# FPGA.net
KiCad netlist of a schematic drawn in Altium Designer
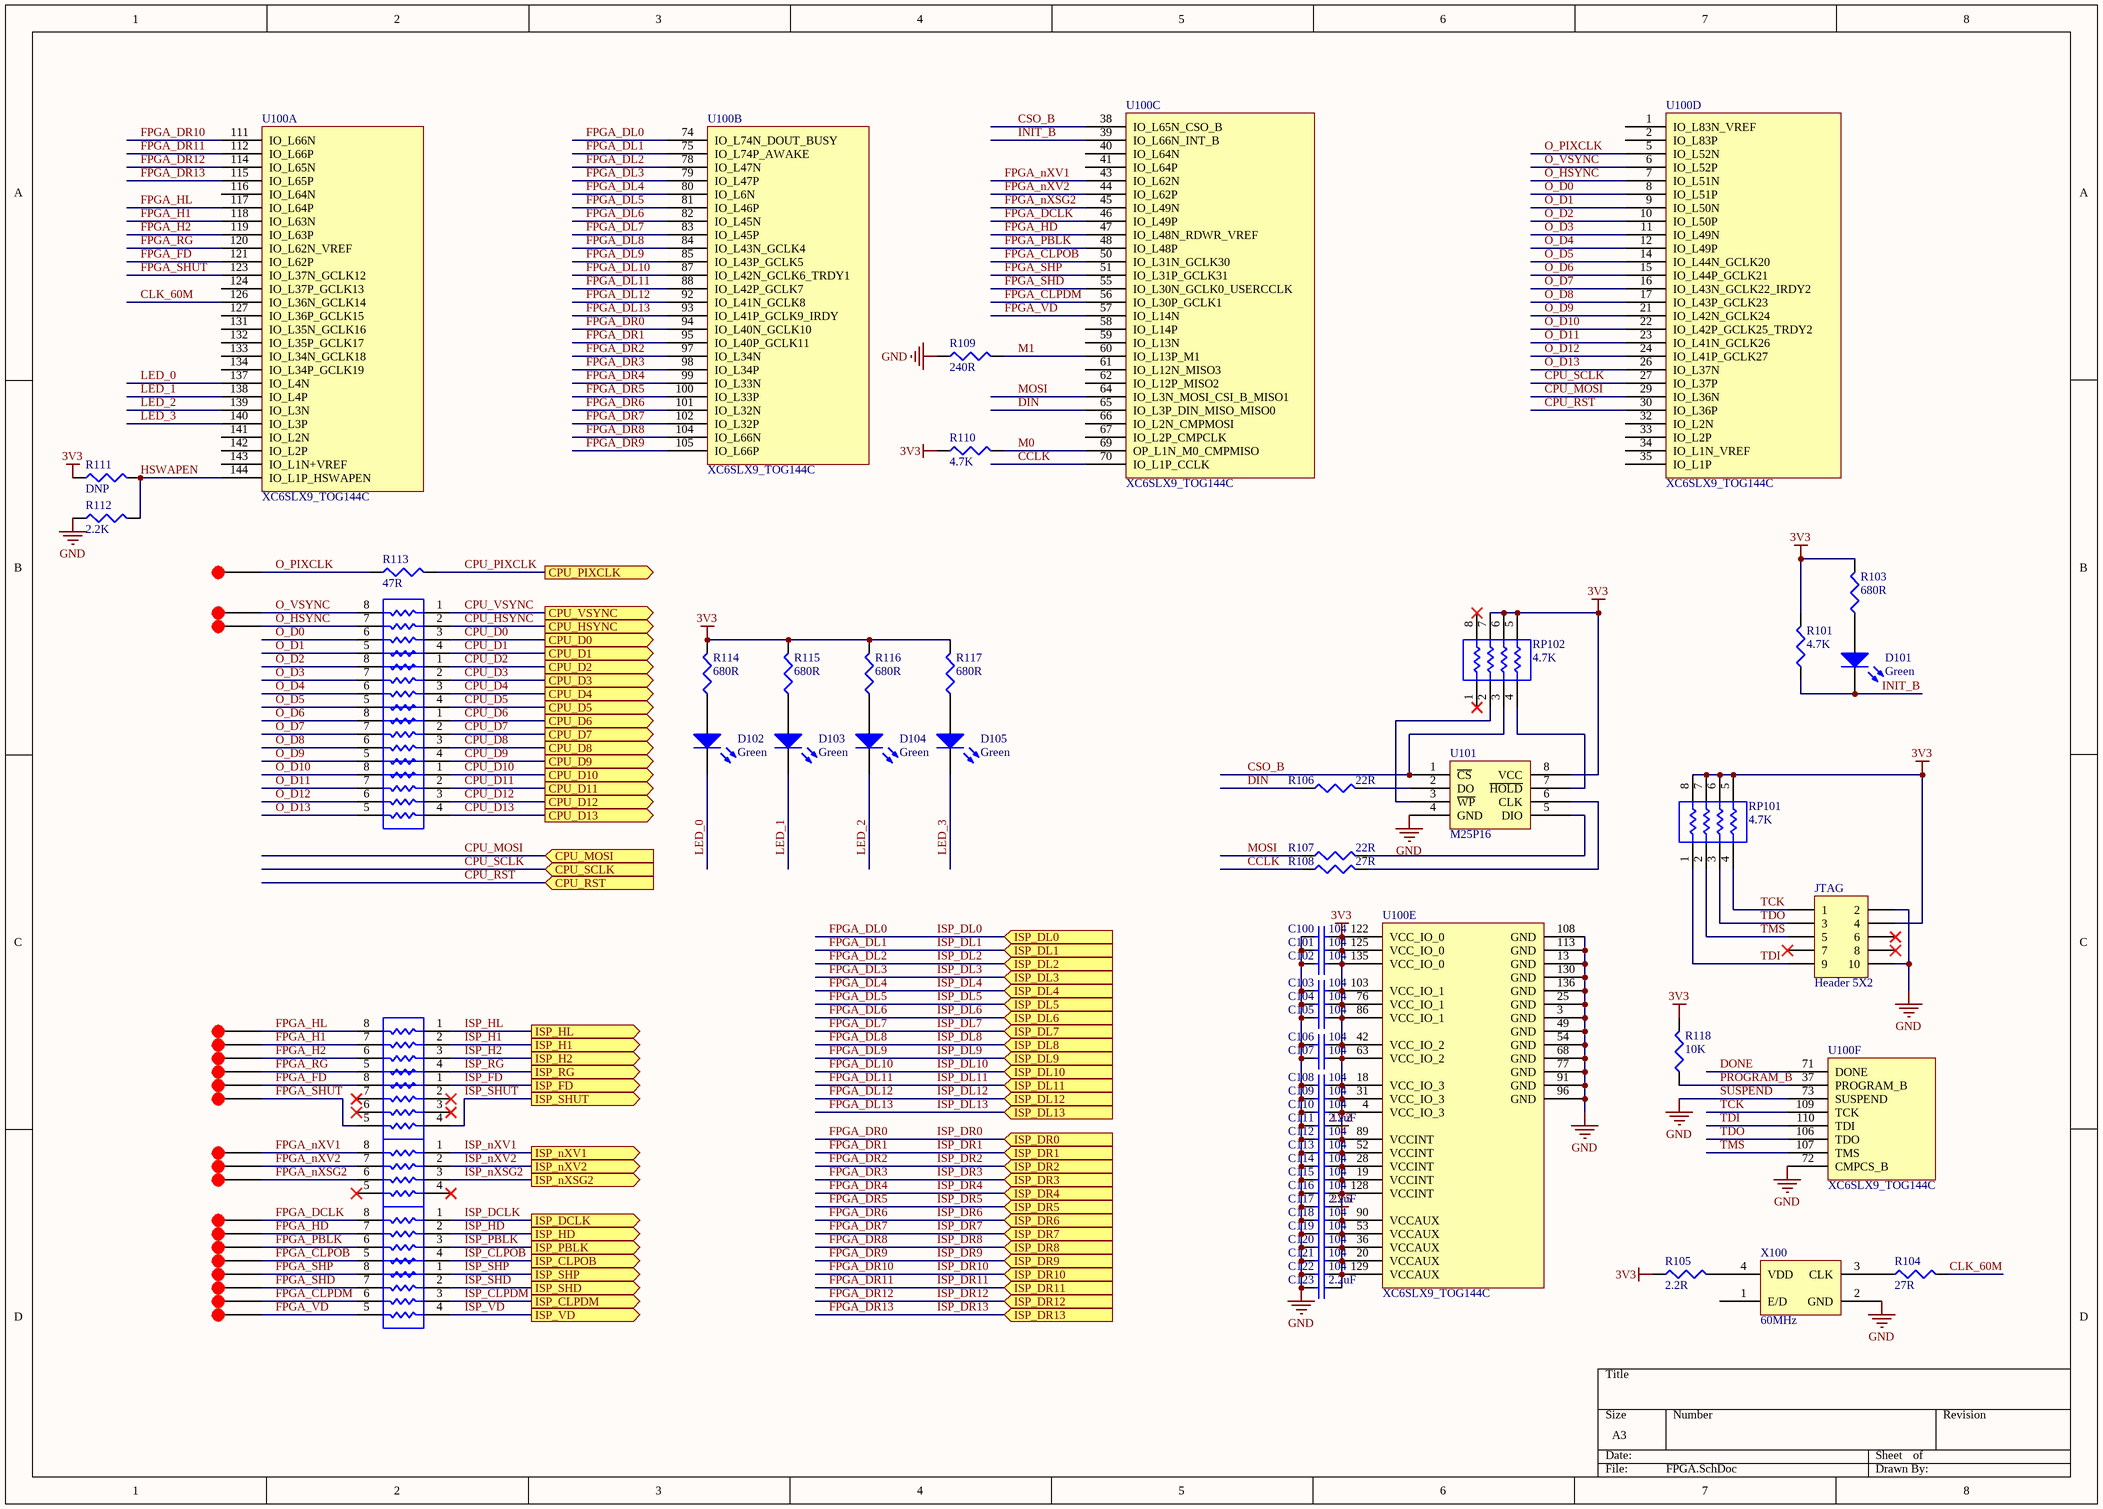
[diagram p0: FPGA.SchDoc]

(export (version "E")
  (design (tool "Eeschema 10.0.6"))
  (components
    (comp (ref "C100")
      (value "104")
      (footprint "C0402")
      (description "Capacitor (Semiconductor SIM Model)")
      (fields (field (name "PUBLISHER") "Altium Limited"))
      (libsource (lib "Miscellaneous Devices") (part "Cap Semi"))
    )
    (comp (ref "C101")
      (value "104")
      (footprint "C0402")
      (description "Capacitor (Semiconductor SIM Model)")
      (fields (field (name "PUBLISHER") "Altium Limited"))
      (libsource (lib "Miscellaneous Devices") (part "Cap Semi"))
    )
    (comp (ref "C102")
      (value "104")
      (footprint "C0402")
      (description "Capacitor (Semiconductor SIM Model)")
      (fields (field (name "PUBLISHER") "Altium Limited"))
      (libsource (lib "Miscellaneous Devices") (part "Cap Semi"))
    )
    (comp (ref "C103")
      (value "104")
      (footprint "C0402")
      (description "Capacitor (Semiconductor SIM Model)")
      (fields (field (name "PUBLISHER") "Altium Limited"))
      (libsource (lib "Miscellaneous Devices") (part "Cap Semi"))
    )
    (comp (ref "C104")
      (value "104")
      (footprint "C0402")
      (description "Capacitor (Semiconductor SIM Model)")
      (fields (field (name "PUBLISHER") "Altium Limited"))
      (libsource (lib "Miscellaneous Devices") (part "Cap Semi"))
    )
    (comp (ref "C105")
      (value "104")
      (footprint "C0402")
      (description "Capacitor (Semiconductor SIM Model)")
      (fields (field (name "PUBLISHER") "Altium Limited"))
      (libsource (lib "Miscellaneous Devices") (part "Cap Semi"))
    )
    (comp (ref "C106")
      (value "104")
      (footprint "C0402")
      (description "Capacitor (Semiconductor SIM Model)")
      (fields (field (name "PUBLISHER") "Altium Limited"))
      (libsource (lib "Miscellaneous Devices") (part "Cap Semi"))
    )
    (comp (ref "C107")
      (value "104")
      (footprint "C0402")
      (description "Capacitor (Semiconductor SIM Model)")
      (fields (field (name "PUBLISHER") "Altium Limited"))
      (libsource (lib "Miscellaneous Devices") (part "Cap Semi"))
    )
    (comp (ref "C108")
      (value "104")
      (footprint "C0402")
      (description "Capacitor (Semiconductor SIM Model)")
      (fields (field (name "PUBLISHER") "Altium Limited"))
      (libsource (lib "Miscellaneous Devices") (part "Cap Semi"))
    )
    (comp (ref "C109")
      (value "104")
      (footprint "C0402")
      (description "Capacitor (Semiconductor SIM Model)")
      (fields (field (name "PUBLISHER") "Altium Limited"))
      (libsource (lib "Miscellaneous Devices") (part "Cap Semi"))
    )
    (comp (ref "C110")
      (value "104")
      (footprint "C0402")
      (description "Capacitor (Semiconductor SIM Model)")
      (fields (field (name "PUBLISHER") "Altium Limited"))
      (libsource (lib "Miscellaneous Devices") (part "Cap Semi"))
    )
    (comp (ref "C111")
      (value "2.2uF")
      (footprint "C0603")
      (description "Capacitor (Semiconductor SIM Model)")
      (fields (field (name "PUBLISHER") "Altium Limited"))
      (libsource (lib "Miscellaneous Devices") (part "Cap Semi"))
    )
    (comp (ref "C112")
      (value "104")
      (footprint "C0402")
      (description "Capacitor (Semiconductor SIM Model)")
      (fields (field (name "PUBLISHER") "Altium Limited"))
      (libsource (lib "Miscellaneous Devices") (part "Cap Semi"))
    )
    (comp (ref "C113")
      (value "104")
      (footprint "C0402")
      (description "Capacitor (Semiconductor SIM Model)")
      (fields (field (name "PUBLISHER") "Altium Limited"))
      (libsource (lib "Miscellaneous Devices") (part "Cap Semi"))
    )
    (comp (ref "C114")
      (value "104")
      (footprint "C0402")
      (description "Capacitor (Semiconductor SIM Model)")
      (fields (field (name "PUBLISHER") "Altium Limited"))
      (libsource (lib "Miscellaneous Devices") (part "Cap Semi"))
    )
    (comp (ref "C115")
      (value "104")
      (footprint "C0402")
      (description "Capacitor (Semiconductor SIM Model)")
      (fields (field (name "PUBLISHER") "Altium Limited"))
      (libsource (lib "Miscellaneous Devices") (part "Cap Semi"))
    )
    (comp (ref "C116")
      (value "104")
      (footprint "C0402")
      (description "Capacitor (Semiconductor SIM Model)")
      (fields (field (name "PUBLISHER") "Altium Limited"))
      (libsource (lib "Miscellaneous Devices") (part "Cap Semi"))
    )
    (comp (ref "C117")
      (value "2.2uF")
      (footprint "C0603")
      (description "Capacitor (Semiconductor SIM Model)")
      (fields (field (name "PUBLISHER") "Altium Limited"))
      (libsource (lib "Miscellaneous Devices") (part "Cap Semi"))
    )
    (comp (ref "C118")
      (value "104")
      (footprint "C0402")
      (description "Capacitor (Semiconductor SIM Model)")
      (fields (field (name "PUBLISHER") "Altium Limited"))
      (libsource (lib "Miscellaneous Devices") (part "Cap Semi"))
    )
    (comp (ref "C119")
      (value "104")
      (footprint "C0402")
      (description "Capacitor (Semiconductor SIM Model)")
      (fields (field (name "PUBLISHER") "Altium Limited"))
      (libsource (lib "Miscellaneous Devices") (part "Cap Semi"))
    )
    (comp (ref "C120")
      (value "104")
      (footprint "C0402")
      (description "Capacitor (Semiconductor SIM Model)")
      (fields (field (name "PUBLISHER") "Altium Limited"))
      (libsource (lib "Miscellaneous Devices") (part "Cap Semi"))
    )
    (comp (ref "C121")
      (value "104")
      (footprint "C0402")
      (description "Capacitor (Semiconductor SIM Model)")
      (fields (field (name "PUBLISHER") "Altium Limited"))
      (libsource (lib "Miscellaneous Devices") (part "Cap Semi"))
    )
    (comp (ref "C122")
      (value "104")
      (footprint "C0402")
      (description "Capacitor (Semiconductor SIM Model)")
      (fields (field (name "PUBLISHER") "Altium Limited"))
      (libsource (lib "Miscellaneous Devices") (part "Cap Semi"))
    )
    (comp (ref "C123")
      (value "2.2uF")
      (footprint "C0603")
      (description "Capacitor (Semiconductor SIM Model)")
      (fields (field (name "PUBLISHER") "Altium Limited"))
      (libsource (lib "Miscellaneous Devices") (part "Cap Semi"))
    )
    (comp (ref "D101")
      (value "Green")
      (footprint "D0805")
      (description "Typical RED, GREEN, YELLOW, AMBER GaAs LED")
      (fields (field (name "PUBLISHER") "Altium Limited"))
      (libsource (lib "Schlib2") (part "SMDLED"))
    )
    (comp (ref "D102")
      (value "Green")
      (footprint "D0805")
      (description "Typical RED, GREEN, YELLOW, AMBER GaAs LED")
      (fields (field (name "PUBLISHER") "Altium Limited"))
      (libsource (lib "Schlib2") (part "SMDLED"))
    )
    (comp (ref "D103")
      (value "Green")
      (footprint "D0805")
      (description "Typical RED, GREEN, YELLOW, AMBER GaAs LED")
      (fields (field (name "PUBLISHER") "Altium Limited"))
      (libsource (lib "Schlib2") (part "SMDLED"))
    )
    (comp (ref "D104")
      (value "Green")
      (footprint "D0805")
      (description "Typical RED, GREEN, YELLOW, AMBER GaAs LED")
      (fields (field (name "PUBLISHER") "Altium Limited"))
      (libsource (lib "Schlib2") (part "SMDLED"))
    )
    (comp (ref "D105")
      (value "Green")
      (footprint "D0805")
      (description "Typical RED, GREEN, YELLOW, AMBER GaAs LED")
      (fields (field (name "PUBLISHER") "Altium Limited"))
      (libsource (lib "Schlib2") (part "SMDLED"))
    )
    (comp (ref "JTAG")
      (value "Header 5X2")
      (footprint "HEADER10")
      (description "Header, 5-Pin, Dual row")
      (fields (field (name "PUBLISHER") "Altium Limited"))
      (libsource (lib "Miscellaneous Connectors") (part "Header 5X2"))
    )
    (comp (ref "R101")
      (value "4.7K")
      (footprint "R0603")
      (description "Resistor")
      (fields (field (name "PUBLISHER") "Altium Limited"))
      (libsource (lib "Miscellaneous Devices") (part "Res3"))
    )
    (comp (ref "R103")
      (value "680R")
      (footprint "R0603")
      (description "Resistor")
      (fields (field (name "PUBLISHER") "Altium Limited"))
      (libsource (lib "Miscellaneous Devices") (part "Res3"))
    )
    (comp (ref "R104")
      (value "27R")
      (footprint "R0603")
      (description "Resistor")
      (fields (field (name "PUBLISHER") "Altium Limited"))
      (libsource (lib "Miscellaneous Devices") (part "Res3"))
    )
    (comp (ref "R105")
      (value "2.2R")
      (footprint "R0603")
      (description "Resistor")
      (fields (field (name "PUBLISHER") "Altium Limited"))
      (libsource (lib "Miscellaneous Devices") (part "Res3"))
    )
    (comp (ref "R106")
      (value "22R")
      (footprint "R0603")
      (description "Resistor")
      (fields (field (name "PUBLISHER") "Altium Limited"))
      (libsource (lib "Miscellaneous Devices") (part "Res3"))
    )
    (comp (ref "R107")
      (value "22R")
      (footprint "R0603")
      (description "Resistor")
      (fields (field (name "PUBLISHER") "Altium Limited"))
      (libsource (lib "Miscellaneous Devices") (part "Res3"))
    )
    (comp (ref "R108")
      (value "27R")
      (footprint "R0603")
      (description "Resistor")
      (fields (field (name "PUBLISHER") "Altium Limited"))
      (libsource (lib "Miscellaneous Devices") (part "Res3"))
    )
    (comp (ref "R109")
      (value "240R")
      (footprint "R0603")
      (description "Resistor")
      (fields (field (name "PUBLISHER") "Altium Limited"))
      (libsource (lib "Miscellaneous Devices") (part "Res3"))
    )
    (comp (ref "R110")
      (value "4.7K")
      (footprint "R0603")
      (description "Resistor")
      (fields (field (name "PUBLISHER") "Altium Limited"))
      (libsource (lib "Miscellaneous Devices") (part "Res3"))
    )
    (comp (ref "R111")
      (value "DNP")
      (footprint "R0603")
      (description "Resistor")
      (fields (field (name "PUBLISHER") "Altium Limited"))
      (libsource (lib "Miscellaneous Devices") (part "Res3"))
    )
    (comp (ref "R112")
      (value "2.2K")
      (footprint "R0603")
      (description "Resistor")
      (fields (field (name "PUBLISHER") "Altium Limited"))
      (libsource (lib "Miscellaneous Devices") (part "Res3"))
    )
    (comp (ref "R113")
      (value "47R")
      (footprint "R0603")
      (description "Resistor")
      (fields (field (name "PUBLISHER") "Altium Limited"))
      (libsource (lib "Miscellaneous Devices") (part "Res3"))
    )
    (comp (ref "R114")
      (value "680R")
      (footprint "R0603")
      (description "Resistor")
      (fields (field (name "PUBLISHER") "Altium Limited"))
      (libsource (lib "Miscellaneous Devices") (part "Res3"))
    )
    (comp (ref "R115")
      (value "680R")
      (footprint "R0603")
      (description "Resistor")
      (fields (field (name "PUBLISHER") "Altium Limited"))
      (libsource (lib "Miscellaneous Devices") (part "Res3"))
    )
    (comp (ref "R116")
      (value "680R")
      (footprint "R0603")
      (description "Resistor")
      (fields (field (name "PUBLISHER") "Altium Limited"))
      (libsource (lib "Miscellaneous Devices") (part "Res3"))
    )
    (comp (ref "R117")
      (value "680R")
      (footprint "R0603")
      (description "Resistor")
      (fields (field (name "PUBLISHER") "Altium Limited"))
      (libsource (lib "Miscellaneous Devices") (part "Res3"))
    )
    (comp (ref "R118")
      (value "10K")
      (footprint "R0603")
      (description "Resistor")
      (fields (field (name "PUBLISHER") "Altium Limited"))
      (libsource (lib "Miscellaneous Devices") (part "Res3"))
    )
    (comp (ref "RP101")
      (value "4.7K")
      (footprint "R0402S4")
      (description "Isolated Resistor Network")
      (fields (field (name "PUBLISHER") "Altium Limited"))
      (libsource (lib "Schlib1") (part "ResPack"))
    )
    (comp (ref "RP102")
      (value "4.7K")
      (footprint "R0402S4")
      (description "Isolated Resistor Network")
      (fields (field (name "PUBLISHER") "Altium Limited"))
      (libsource (lib "Schlib1") (part "ResPack"))
    )
    (comp (ref "RP103")
      (value "22R")
      (footprint "R0402S4")
      (description "Isolated Resistor Network")
      (fields (field (name "PUBLISHER") "Altium Limited"))
      (libsource (lib "Schlib1") (part "ResPack"))
    )
    (comp (ref "RP104")
      (value "22R")
      (footprint "R0402S4")
      (description "Isolated Resistor Network")
      (fields (field (name "PUBLISHER") "Altium Limited"))
      (libsource (lib "Schlib1") (part "ResPack"))
    )
    (comp (ref "RP105")
      (value "22R")
      (footprint "R0402S4")
      (description "Isolated Resistor Network")
      (fields (field (name "PUBLISHER") "Altium Limited"))
      (libsource (lib "Schlib1") (part "ResPack"))
    )
    (comp (ref "RP106")
      (value "22R")
      (footprint "R0402S4")
      (description "Isolated Resistor Network")
      (fields (field (name "PUBLISHER") "Altium Limited"))
      (libsource (lib "Schlib1") (part "ResPack"))
    )
    (comp (ref "RP107")
      (value "22R")
      (footprint "R0402S4")
      (description "Isolated Resistor Network")
      (fields (field (name "PUBLISHER") "Altium Limited"))
      (libsource (lib "Schlib1") (part "ResPack"))
    )
    (comp (ref "RP108")
      (value "22R")
      (footprint "R0402S4")
      (description "Isolated Resistor Network")
      (fields (field (name "PUBLISHER") "Altium Limited"))
      (libsource (lib "Schlib1") (part "ResPack"))
    )
    (comp (ref "RP109")
      (value "22R")
      (footprint "R0402S4")
      (description "Isolated Resistor Network")
      (fields (field (name "PUBLISHER") "Altium Limited"))
      (libsource (lib "Schlib1") (part "ResPack"))
    )
    (comp (ref "RP110")
      (value "22R")
      (footprint "R0402S4")
      (description "Isolated Resistor Network")
      (fields (field (name "PUBLISHER") "Altium Limited"))
      (libsource (lib "Schlib1") (part "ResPack"))
    )
    (comp (ref "RP111")
      (value "22R")
      (footprint "R0402S4")
      (description "Isolated Resistor Network")
      (fields (field (name "PUBLISHER") "Altium Limited"))
      (libsource (lib "Schlib1") (part "ResPack"))
    )
    (comp (ref "TP0") (value "TestPoint") (footprint "T_0_7") (libsource (lib "Schlib1") (part "TestPoint")))
    (comp (ref "TP1") (value "TestPoint") (footprint "T_0_7") (libsource (lib "Schlib1") (part "TestPoint")))
    (comp (ref "TP2") (value "TestPoint") (footprint "T_0_7") (libsource (lib "Schlib1") (part "TestPoint")))
    (comp (ref "TP3") (value "TestPoint") (footprint "T_0_7") (libsource (lib "Schlib1") (part "TestPoint")))
    (comp (ref "TP4") (value "TestPoint") (footprint "T_0_7") (libsource (lib "Schlib1") (part "TestPoint")))
    (comp (ref "TP5") (value "TestPoint") (footprint "T_0_7") (libsource (lib "Schlib1") (part "TestPoint")))
    (comp (ref "TP6") (value "TestPoint") (footprint "T_0_7") (libsource (lib "Schlib1") (part "TestPoint")))
    (comp (ref "TP7") (value "TestPoint") (footprint "T_0_7") (libsource (lib "Schlib1") (part "TestPoint")))
    (comp (ref "TP8") (value "TestPoint") (footprint "T_0_7") (libsource (lib "Schlib1") (part "TestPoint")))
    (comp (ref "TP9") (value "TestPoint") (footprint "T_0_7") (libsource (lib "Schlib1") (part "TestPoint")))
    (comp (ref "TP10") (value "TestPoint") (footprint "T_0_7") (libsource (lib "Schlib1") (part "TestPoint")))
    (comp (ref "TP11") (value "TestPoint") (footprint "T_0_7") (libsource (lib "Schlib1") (part "TestPoint")))
    (comp (ref "TP12") (value "TestPoint") (footprint "T_0_7") (libsource (lib "Schlib1") (part "TestPoint")))
    (comp (ref "TP13") (value "TestPoint") (footprint "T_0_7") (libsource (lib "Schlib1") (part "TestPoint")))
    (comp (ref "TP14") (value "TestPoint") (footprint "T_0_7") (libsource (lib "Schlib1") (part "TestPoint")))
    (comp (ref "TP15") (value "TestPoint") (footprint "T_0_7") (libsource (lib "Schlib1") (part "TestPoint")))
    (comp (ref "TP16") (value "TestPoint") (footprint "T_0_7") (libsource (lib "Schlib1") (part "TestPoint")))
    (comp (ref "TP17") (value "TestPoint") (footprint "T_0_7") (libsource (lib "Schlib1") (part "TestPoint")))
    (comp (ref "TP18") (value "TestPoint") (footprint "T_0_7") (libsource (lib "Schlib1") (part "TestPoint")))
    (comp (ref "TP19") (value "TestPoint") (footprint "T_0_7") (libsource (lib "Schlib1") (part "TestPoint")))
    (comp (ref "U100")
      (value "XC6SLX9_TOG144C")
      (footprint "TQFP144")
      (libsource (lib "Schlib1") (part "XC6SLX9_TOG144C"))
    )
    (comp (ref "U101") (value "M25P16") (footprint "SOP-8") (libsource (lib "Schlib1") (part "W25X16")))
    (comp (ref "X100") (value "60MHz") (footprint "CRY_D3225") (libsource (lib "Schlib1") (part "XTAL_5X7")))
  )
  (nets
    (net (code "1") (name "/CCLK") (class "Default")
      (node (ref "R108") (pin "1") (pinfunction "1_1") (pintype "passive"))
      (node (ref "U100") (pin "70") (pinfunction "IO_L1P_CCLK_70") (pintype "passive"))
    )
    (net (code "2") (name "/CLK_60M") (class "Default")
      (node (ref "R104") (pin "2") (pinfunction "2_2") (pintype "passive"))
      (node (ref "U100") (pin "126") (pinfunction "IO_L36N_GCLK14_126") (pintype "passive"))
    )
    (net (code "3") (name "/CPU_D0") (class "Default")
      (node (ref "RP108") (pin "3") (pinfunction "3_3") (pintype "passive"))
    )
    (net (code "4") (name "/CPU_D1") (class "Default")
      (node (ref "RP108") (pin "4") (pinfunction "4_4") (pintype "passive"))
    )
    (net (code "5") (name "/CPU_D2") (class "Default")
      (node (ref "RP109") (pin "1") (pinfunction "1_1") (pintype "passive"))
    )
    (net (code "6") (name "/CPU_D3") (class "Default")
      (node (ref "RP109") (pin "2") (pinfunction "2_2") (pintype "passive"))
    )
    (net (code "7") (name "/CPU_D4") (class "Default")
      (node (ref "RP109") (pin "3") (pinfunction "3_3") (pintype "passive"))
    )
    (net (code "8") (name "/CPU_D5") (class "Default")
      (node (ref "RP109") (pin "4") (pinfunction "4_4") (pintype "passive"))
    )
    (net (code "9") (name "/CPU_D6") (class "Default")
      (node (ref "RP110") (pin "1") (pinfunction "1_1") (pintype "passive"))
    )
    (net (code "10") (name "/CPU_D7") (class "Default")
      (node (ref "RP110") (pin "2") (pinfunction "2_2") (pintype "passive"))
    )
    (net (code "11") (name "/CPU_D8") (class "Default")
      (node (ref "RP110") (pin "3") (pinfunction "3_3") (pintype "passive"))
    )
    (net (code "12") (name "/CPU_D9") (class "Default")
      (node (ref "RP110") (pin "4") (pinfunction "4_4") (pintype "passive"))
    )
    (net (code "13") (name "/CPU_D10") (class "Default")
      (node (ref "RP111") (pin "1") (pinfunction "1_1") (pintype "passive"))
    )
    (net (code "14") (name "/CPU_D11") (class "Default")
      (node (ref "RP111") (pin "2") (pinfunction "2_2") (pintype "passive"))
    )
    (net (code "15") (name "/CPU_D12") (class "Default")
      (node (ref "RP111") (pin "3") (pinfunction "3_3") (pintype "passive"))
    )
    (net (code "16") (name "/CPU_D13") (class "Default")
      (node (ref "RP111") (pin "4") (pinfunction "4_4") (pintype "passive"))
    )
    (net (code "17") (name "/CPU_HSYNC") (class "Default")
      (node (ref "RP108") (pin "2") (pinfunction "2_2") (pintype "passive"))
    )
    (net (code "18") (name "/CPU_MOSI") (class "Default")
      (node (ref "U100") (pin "29") (pinfunction "IO_L36N_29") (pintype "passive"))
    )
    (net (code "19") (name "/CPU_PIXCLK") (class "Default")
      (node (ref "R113") (pin "2") (pinfunction "2_2") (pintype "passive"))
    )
    (net (code "20") (name "/CPU_RST") (class "Default")
      (node (ref "U100") (pin "30") (pinfunction "IO_L36P_30") (pintype "passive"))
    )
    (net (code "21") (name "/CPU_SCLK") (class "Default")
      (node (ref "U100") (pin "27") (pinfunction "IO_L37P_27") (pintype "passive"))
    )
    (net (code "22") (name "/CPU_VSYNC") (class "Default")
      (node (ref "RP108") (pin "1") (pinfunction "1_1") (pintype "passive"))
    )
    (net (code "23") (name "/CSO_B") (class "Default")
      (node (ref "RP102") (pin "3") (pinfunction "3_3") (pintype "passive"))
      (node (ref "U100") (pin "38") (pinfunction "IO_L65N_CSO_B_38") (pintype "passive"))
      (node (ref "U101") (pin "1") (pinfunction "~{CS}_1") (pintype "passive"))
    )
    (net (code "24") (name "/DIN") (class "Default")
      (node (ref "R106") (pin "1") (pinfunction "1_1") (pintype "passive"))
      (node (ref "U100") (pin "65") (pinfunction "IO_L3P_DIN_MISO_MISO0_65") (pintype "passive"))
    )
    (net (code "25") (name "/DONE") (class "Default")
      (node (ref "U100") (pin "71") (pinfunction "DONE_71") (pintype "passive"))
    )
    (net (code "26") (name "/FPGA_CLPDM") (class "Default")
      (node (ref "RP106") (pin "6") (pinfunction "6_6") (pintype "passive"))
      (node (ref "TP15") (pin "1") (pinfunction "CMPCS_B_1") (pintype "passive"))
      (node (ref "U100") (pin "56") (pinfunction "IO_L30P_GCLK1_56") (pintype "passive"))
    )
    (net (code "27") (name "/FPGA_CLPOB") (class "Default")
      (node (ref "RP105") (pin "5") (pinfunction "5_5") (pintype "passive"))
      (node (ref "TP12") (pin "1") (pinfunction "CMPCS_B_1") (pintype "passive"))
      (node (ref "U100") (pin "50") (pinfunction "IO_L31N_GCLK30_50") (pintype "passive"))
    )
    (net (code "28") (name "/FPGA_DCLK") (class "Default")
      (node (ref "RP105") (pin "8") (pinfunction "8_8") (pintype "passive"))
      (node (ref "TP9") (pin "1") (pinfunction "CMPCS_B_1") (pintype "passive"))
      (node (ref "U100") (pin "46") (pinfunction "IO_L49P_46") (pintype "passive"))
    )
    (net (code "29") (name "/FPGA_DL0") (class "Default")
      (node (ref "U100") (pin "74") (pinfunction "IO_L74N_DOUT_BUSY_74") (pintype "passive"))
    )
    (net (code "30") (name "/FPGA_DL1") (class "Default")
      (node (ref "U100") (pin "75") (pinfunction "IO_L74P_AWAKE_75") (pintype "passive"))
    )
    (net (code "31") (name "/FPGA_DL2") (class "Default")
      (node (ref "U100") (pin "78") (pinfunction "IO_L47N_78") (pintype "passive"))
    )
    (net (code "32") (name "/FPGA_DL3") (class "Default")
      (node (ref "U100") (pin "79") (pinfunction "IO_L47P_79") (pintype "passive"))
    )
    (net (code "33") (name "/FPGA_DL4") (class "Default")
      (node (ref "U100") (pin "80") (pinfunction "IO_L6N_80") (pintype "passive"))
    )
    (net (code "34") (name "/FPGA_DL5") (class "Default")
      (node (ref "U100") (pin "81") (pinfunction "IO_L46P_81") (pintype "passive"))
    )
    (net (code "35") (name "/FPGA_DL6") (class "Default")
      (node (ref "U100") (pin "82") (pinfunction "IO_L45N_82") (pintype "passive"))
    )
    (net (code "36") (name "/FPGA_DL7") (class "Default")
      (node (ref "U100") (pin "83") (pinfunction "IO_L45P_83") (pintype "passive"))
    )
    (net (code "37") (name "/FPGA_DL8") (class "Default")
      (node (ref "U100") (pin "84") (pinfunction "IO_L43N_GCLK4_84") (pintype "passive"))
    )
    (net (code "38") (name "/FPGA_DL9") (class "Default")
      (node (ref "U100") (pin "85") (pinfunction "IO_L43P_GCLK5_85") (pintype "passive"))
    )
    (net (code "39") (name "/FPGA_DL10") (class "Default")
      (node (ref "U100") (pin "87") (pinfunction "IO_L42N_GCLK6_TRDY1_87") (pintype "passive"))
    )
    (net (code "40") (name "/FPGA_DL11") (class "Default")
      (node (ref "U100") (pin "88") (pinfunction "IO_L42P_GCLK7_88") (pintype "passive"))
    )
    (net (code "41") (name "/FPGA_DL12") (class "Default")
      (node (ref "U100") (pin "92") (pinfunction "IO_L41N_GCLK8_92") (pintype "passive"))
    )
    (net (code "42") (name "/FPGA_DL13") (class "Default")
      (node (ref "U100") (pin "93") (pinfunction "IO_L41P_GCLK9_IRDY_93") (pintype "passive"))
    )
    (net (code "43") (name "/FPGA_DR0") (class "Default")
      (node (ref "U100") (pin "94") (pinfunction "IO_L40N_GCLK10_94") (pintype "passive"))
    )
    (net (code "44") (name "/FPGA_DR1") (class "Default")
      (node (ref "U100") (pin "95") (pinfunction "IO_L40P_GCLK11_95") (pintype "passive"))
    )
    (net (code "45") (name "/FPGA_DR2") (class "Default")
      (node (ref "U100") (pin "97") (pinfunction "IO_L34N_97") (pintype "passive"))
    )
    (net (code "46") (name "/FPGA_DR3") (class "Default")
      (node (ref "U100") (pin "98") (pinfunction "IO_L34P_98") (pintype "passive"))
    )
    (net (code "47") (name "/FPGA_DR4") (class "Default")
      (node (ref "U100") (pin "99") (pinfunction "IO_L33N_99") (pintype "passive"))
    )
    (net (code "48") (name "/FPGA_DR5") (class "Default")
      (node (ref "U100") (pin "100") (pinfunction "IO_L33P_100") (pintype "passive"))
    )
    (net (code "49") (name "/FPGA_DR6") (class "Default")
      (node (ref "U100") (pin "101") (pinfunction "IO_L32N_101") (pintype "passive"))
    )
    (net (code "50") (name "/FPGA_DR7") (class "Default")
      (node (ref "U100") (pin "102") (pinfunction "IO_L32P_102") (pintype "passive"))
    )
    (net (code "51") (name "/FPGA_DR8") (class "Default")
      (node (ref "U100") (pin "104") (pinfunction "IO_L66N_104") (pintype "passive"))
    )
    (net (code "52") (name "/FPGA_DR9") (class "Default")
      (node (ref "U100") (pin "105") (pinfunction "IO_L66P_105") (pintype "passive"))
    )
    (net (code "53") (name "/FPGA_DR10") (class "Default")
      (node (ref "U100") (pin "111") (pinfunction "IO_L66N_111") (pintype "passive"))
    )
    (net (code "54") (name "/FPGA_DR11") (class "Default")
      (node (ref "U100") (pin "112") (pinfunction "IO_L66P_112") (pintype "passive"))
    )
    (net (code "55") (name "/FPGA_DR12") (class "Default")
      (node (ref "U100") (pin "114") (pinfunction "IO_L65N_114") (pintype "passive"))
    )
    (net (code "56") (name "/FPGA_DR13") (class "Default")
      (node (ref "U100") (pin "115") (pinfunction "IO_L65P_115") (pintype "passive"))
    )
    (net (code "57") (name "/FPGA_FD") (class "Default")
      (node (ref "RP107") (pin "8") (pinfunction "8_8") (pintype "passive"))
      (node (ref "TP4") (pin "1") (pinfunction "CMPCS_B_1") (pintype "passive"))
      (node (ref "U100") (pin "121") (pinfunction "IO_L62P_121") (pintype "passive"))
    )
    (net (code "58") (name "/FPGA_H1") (class "Default")
      (node (ref "RP103") (pin "7") (pinfunction "7_7") (pintype "passive"))
      (node (ref "TP1") (pin "1") (pinfunction "CMPCS_B_1") (pintype "passive"))
      (node (ref "U100") (pin "118") (pinfunction "IO_L63N_118") (pintype "passive"))
    )
    (net (code "59") (name "/FPGA_H2") (class "Default")
      (node (ref "RP103") (pin "6") (pinfunction "6_6") (pintype "passive"))
      (node (ref "TP2") (pin "1") (pinfunction "CMPCS_B_1") (pintype "passive"))
      (node (ref "U100") (pin "119") (pinfunction "IO_L63P_119") (pintype "passive"))
    )
    (net (code "60") (name "/FPGA_HD") (class "Default")
      (node (ref "RP105") (pin "7") (pinfunction "7_7") (pintype "passive"))
      (node (ref "TP10") (pin "1") (pinfunction "CMPCS_B_1") (pintype "passive"))
      (node (ref "U100") (pin "47") (pinfunction "IO_L48N_RDWR_VREF_47") (pintype "passive"))
    )
    (net (code "61") (name "/FPGA_HL") (class "Default")
      (node (ref "RP103") (pin "8") (pinfunction "8_8") (pintype "passive"))
      (node (ref "TP0") (pin "1") (pinfunction "CMPCS_B_1") (pintype "passive"))
      (node (ref "U100") (pin "117") (pinfunction "IO_L64P_117") (pintype "passive"))
    )
    (net (code "62") (name "/FPGA_PBLK") (class "Default")
      (node (ref "RP105") (pin "6") (pinfunction "6_6") (pintype "passive"))
      (node (ref "TP11") (pin "1") (pinfunction "CMPCS_B_1") (pintype "passive"))
      (node (ref "U100") (pin "48") (pinfunction "IO_L48P_48") (pintype "passive"))
    )
    (net (code "63") (name "/FPGA_RG") (class "Default")
      (node (ref "RP103") (pin "5") (pinfunction "5_5") (pintype "passive"))
      (node (ref "TP3") (pin "1") (pinfunction "CMPCS_B_1") (pintype "passive"))
      (node (ref "U100") (pin "120") (pinfunction "IO_L62N_VREF_120") (pintype "passive"))
    )
    (net (code "64") (name "/FPGA_SHD") (class "Default")
      (node (ref "RP106") (pin "7") (pinfunction "7_7") (pintype "passive"))
      (node (ref "TP14") (pin "1") (pinfunction "CMPCS_B_1") (pintype "passive"))
      (node (ref "U100") (pin "55") (pinfunction "IO_L30N_GCLK0_USERCCLK_55") (pintype "passive"))
    )
    (net (code "65") (name "/FPGA_SHP") (class "Default")
      (node (ref "RP106") (pin "8") (pinfunction "8_8") (pintype "passive"))
      (node (ref "TP13") (pin "1") (pinfunction "CMPCS_B_1") (pintype "passive"))
      (node (ref "U100") (pin "51") (pinfunction "IO_L31P_GCLK31_51") (pintype "passive"))
    )
    (net (code "66") (name "/FPGA_SHUT") (class "Default")
      (node (ref "RP107") (pin "5") (pinfunction "5_5") (pintype "passive"))
      (node (ref "TP5") (pin "1") (pinfunction "CMPCS_B_1") (pintype "passive"))
      (node (ref "U100") (pin "123") (pinfunction "IO_L37N_GCLK12_123") (pintype "passive"))
    )
    (net (code "67") (name "/FPGA_VD") (class "Default")
      (node (ref "RP106") (pin "5") (pinfunction "5_5") (pintype "passive"))
      (node (ref "TP16") (pin "1") (pinfunction "CMPCS_B_1") (pintype "passive"))
      (node (ref "U100") (pin "57") (pinfunction "IO_L14N_57") (pintype "passive"))
    )
    (net (code "68") (name "/FPGA_nXSG2") (class "Default")
      (node (ref "RP104") (pin "6") (pinfunction "6_6") (pintype "passive"))
      (node (ref "TP8") (pin "1") (pinfunction "CMPCS_B_1") (pintype "passive"))
      (node (ref "U100") (pin "45") (pinfunction "IO_L49N_45") (pintype "passive"))
    )
    (net (code "69") (name "/FPGA_nXV1") (class "Default")
      (node (ref "RP104") (pin "8") (pinfunction "8_8") (pintype "passive"))
      (node (ref "TP6") (pin "1") (pinfunction "CMPCS_B_1") (pintype "passive"))
      (node (ref "U100") (pin "43") (pinfunction "IO_L62N_43") (pintype "passive"))
    )
    (net (code "70") (name "/FPGA_nXV2") (class "Default")
      (node (ref "RP104") (pin "7") (pinfunction "7_7") (pintype "passive"))
      (node (ref "TP7") (pin "1") (pinfunction "CMPCS_B_1") (pintype "passive"))
      (node (ref "U100") (pin "44") (pinfunction "IO_L62P_44") (pintype "passive"))
    )
    (net (code "71") (name "/HSWAPEN") (class "Default")
      (node (ref "R111") (pin "2") (pinfunction "2_2") (pintype "passive"))
      (node (ref "R112") (pin "2") (pinfunction "2_2") (pintype "passive"))
      (node (ref "U100") (pin "144") (pinfunction "IO_L1P_HSWAPEN_144") (pintype "passive"))
    )
    (net (code "72") (name "/INIT_B") (class "Default")
      (node (ref "D101") (pin "2") (pinfunction "K_2") (pintype "passive"))
      (node (ref "R101") (pin "1") (pinfunction "1_1") (pintype "passive"))
      (node (ref "U100") (pin "39") (pinfunction "IO_L66N_INT_B_39") (pintype "passive"))
    )
    (net (code "73") (name "/ISP_CLPDM") (class "Default")
      (node (ref "RP106") (pin "3") (pinfunction "3_3") (pintype "passive"))
    )
    (net (code "74") (name "/ISP_CLPOB") (class "Default")
      (node (ref "RP105") (pin "4") (pinfunction "4_4") (pintype "passive"))
    )
    (net (code "75") (name "/ISP_DCLK") (class "Default")
      (node (ref "RP105") (pin "1") (pinfunction "1_1") (pintype "passive"))
    )
    (net (code "76") (name "/ISP_FD") (class "Default")
      (node (ref "RP107") (pin "1") (pinfunction "1_1") (pintype "passive"))
    )
    (net (code "77") (name "/ISP_H1") (class "Default")
      (node (ref "RP103") (pin "2") (pinfunction "2_2") (pintype "passive"))
    )
    (net (code "78") (name "/ISP_H2") (class "Default")
      (node (ref "RP103") (pin "3") (pinfunction "3_3") (pintype "passive"))
    )
    (net (code "79") (name "/ISP_HD") (class "Default")
      (node (ref "RP105") (pin "2") (pinfunction "2_2") (pintype "passive"))
    )
    (net (code "80") (name "/ISP_HL") (class "Default")
      (node (ref "RP103") (pin "1") (pinfunction "1_1") (pintype "passive"))
    )
    (net (code "81") (name "/ISP_PBLK") (class "Default")
      (node (ref "RP105") (pin "3") (pinfunction "3_3") (pintype "passive"))
    )
    (net (code "82") (name "/ISP_RG") (class "Default")
      (node (ref "RP103") (pin "4") (pinfunction "4_4") (pintype "passive"))
    )
    (net (code "83") (name "/ISP_SHD") (class "Default")
      (node (ref "RP106") (pin "2") (pinfunction "2_2") (pintype "passive"))
    )
    (net (code "84") (name "/ISP_SHP") (class "Default")
      (node (ref "RP106") (pin "1") (pinfunction "1_1") (pintype "passive"))
    )
    (net (code "85") (name "/ISP_SHUT") (class "Default")
      (node (ref "RP107") (pin "4") (pinfunction "4_4") (pintype "passive"))
    )
    (net (code "86") (name "/ISP_VD") (class "Default")
      (node (ref "RP106") (pin "4") (pinfunction "4_4") (pintype "passive"))
    )
    (net (code "87") (name "/ISP_nXSG2") (class "Default")
      (node (ref "RP104") (pin "3") (pinfunction "3_3") (pintype "passive"))
    )
    (net (code "88") (name "/ISP_nXV1") (class "Default")
      (node (ref "RP104") (pin "1") (pinfunction "1_1") (pintype "passive"))
    )
    (net (code "89") (name "/ISP_nXV2") (class "Default")
      (node (ref "RP104") (pin "2") (pinfunction "2_2") (pintype "passive"))
    )
    (net (code "90") (name "/LED_0") (class "Default")
      (node (ref "D102") (pin "2") (pinfunction "K_2") (pintype "passive"))
      (node (ref "U100") (pin "137") (pinfunction "IO_L4N_137") (pintype "passive"))
    )
    (net (code "91") (name "/LED_1") (class "Default")
      (node (ref "D103") (pin "2") (pinfunction "K_2") (pintype "passive"))
      (node (ref "U100") (pin "138") (pinfunction "IO_L4P_138") (pintype "passive"))
    )
    (net (code "92") (name "/LED_2") (class "Default")
      (node (ref "D104") (pin "2") (pinfunction "K_2") (pintype "passive"))
      (node (ref "U100") (pin "139") (pinfunction "IO_L3N_139") (pintype "passive"))
    )
    (net (code "93") (name "/LED_3") (class "Default")
      (node (ref "D105") (pin "2") (pinfunction "K_2") (pintype "passive"))
      (node (ref "U100") (pin "140") (pinfunction "IO_L3P_140") (pintype "passive"))
    )
    (net (code "94") (name "/M0") (class "Default")
      (node (ref "R110") (pin "2") (pinfunction "2_2") (pintype "passive"))
      (node (ref "U100") (pin "69") (pinfunction "OP_L1N_M0_CMPMISO_69") (pintype "passive"))
    )
    (net (code "95") (name "/M1") (class "Default")
      (node (ref "R109") (pin "2") (pinfunction "2_2") (pintype "passive"))
      (node (ref "U100") (pin "60") (pinfunction "IO_L13P_M1_60") (pintype "passive"))
    )
    (net (code "96") (name "/MOSI") (class "Default")
      (node (ref "R107") (pin "1") (pinfunction "1_1") (pintype "passive"))
      (node (ref "U100") (pin "64") (pinfunction "IO_L3N_MOSI_CSI_B_MISO1_64") (pintype "passive"))
    )
    (net (code "97") (name "/O_D0") (class "Default")
      (node (ref "RP108") (pin "6") (pinfunction "6_6") (pintype "passive"))
      (node (ref "U100") (pin "8") (pinfunction "IO_L51P_8") (pintype "passive"))
    )
    (net (code "98") (name "/O_D1") (class "Default")
      (node (ref "RP108") (pin "5") (pinfunction "5_5") (pintype "passive"))
      (node (ref "U100") (pin "9") (pinfunction "IO_L50N_9") (pintype "passive"))
    )
    (net (code "99") (name "/O_D2") (class "Default")
      (node (ref "RP109") (pin "8") (pinfunction "8_8") (pintype "passive"))
      (node (ref "U100") (pin "10") (pinfunction "IO_L50P_10") (pintype "passive"))
    )
    (net (code "100") (name "/O_D3") (class "Default")
      (node (ref "RP109") (pin "7") (pinfunction "7_7") (pintype "passive"))
      (node (ref "U100") (pin "11") (pinfunction "IO_L49N_11") (pintype "passive"))
    )
    (net (code "101") (name "/O_D4") (class "Default")
      (node (ref "RP109") (pin "6") (pinfunction "6_6") (pintype "passive"))
      (node (ref "U100") (pin "12") (pinfunction "IO_L49P_12") (pintype "passive"))
    )
    (net (code "102") (name "/O_D5") (class "Default")
      (node (ref "RP109") (pin "5") (pinfunction "5_5") (pintype "passive"))
      (node (ref "U100") (pin "14") (pinfunction "IO_L44N_GCLK20_14") (pintype "passive"))
    )
    (net (code "103") (name "/O_D6") (class "Default")
      (node (ref "RP110") (pin "8") (pinfunction "8_8") (pintype "passive"))
      (node (ref "U100") (pin "15") (pinfunction "IO_L44P_GCLK21_15") (pintype "passive"))
    )
    (net (code "104") (name "/O_D7") (class "Default")
      (node (ref "RP110") (pin "7") (pinfunction "7_7") (pintype "passive"))
      (node (ref "U100") (pin "16") (pinfunction "IO_L43N_GCLK22_IRDY2_16") (pintype "passive"))
    )
    (net (code "105") (name "/O_D8") (class "Default")
      (node (ref "RP110") (pin "6") (pinfunction "6_6") (pintype "passive"))
      (node (ref "U100") (pin "17") (pinfunction "IO_L43P_GCLK23_17") (pintype "passive"))
    )
    (net (code "106") (name "/O_D9") (class "Default")
      (node (ref "RP110") (pin "5") (pinfunction "5_5") (pintype "passive"))
      (node (ref "U100") (pin "21") (pinfunction "IO_L42N_GCLK24_21") (pintype "passive"))
    )
    (net (code "107") (name "/O_D10") (class "Default")
      (node (ref "RP111") (pin "8") (pinfunction "8_8") (pintype "passive"))
      (node (ref "U100") (pin "22") (pinfunction "IO_L42P_GCLK25_TRDY2_22") (pintype "passive"))
    )
    (net (code "108") (name "/O_D11") (class "Default")
      (node (ref "RP111") (pin "7") (pinfunction "7_7") (pintype "passive"))
      (node (ref "U100") (pin "23") (pinfunction "IO_L41N_GCLK26_23") (pintype "passive"))
    )
    (net (code "109") (name "/O_D12") (class "Default")
      (node (ref "RP111") (pin "6") (pinfunction "6_6") (pintype "passive"))
      (node (ref "U100") (pin "24") (pinfunction "IO_L41P_GCLK27_24") (pintype "passive"))
    )
    (net (code "110") (name "/O_D13") (class "Default")
      (node (ref "RP111") (pin "5") (pinfunction "5_5") (pintype "passive"))
      (node (ref "U100") (pin "26") (pinfunction "IO_L37N_26") (pintype "passive"))
    )
    (net (code "111") (name "/O_HSYNC") (class "Default")
      (node (ref "RP108") (pin "7") (pinfunction "7_7") (pintype "passive"))
      (node (ref "TP19") (pin "1") (pinfunction "CMPCS_B_1") (pintype "passive"))
      (node (ref "U100") (pin "7") (pinfunction "IO_L51N_7") (pintype "passive"))
    )
    (net (code "112") (name "/O_PIXCLK") (class "Default")
      (node (ref "R113") (pin "1") (pinfunction "1_1") (pintype "passive"))
      (node (ref "TP17") (pin "1") (pinfunction "CMPCS_B_1") (pintype "passive"))
      (node (ref "U100") (pin "5") (pinfunction "IO_L52N_5") (pintype "passive"))
    )
    (net (code "113") (name "/O_VSYNC") (class "Default")
      (node (ref "RP108") (pin "8") (pinfunction "8_8") (pintype "passive"))
      (node (ref "TP18") (pin "1") (pinfunction "CMPCS_B_1") (pintype "passive"))
      (node (ref "U100") (pin "6") (pinfunction "IO_L52P_6") (pintype "passive"))
    )
    (net (code "114") (name "/PROGRAM_B") (class "Default")
      (node (ref "R118") (pin "1") (pinfunction "1_1") (pintype "passive"))
      (node (ref "U100") (pin "37") (pinfunction "PROGRAM_B_37") (pintype "passive"))
    )
    (net (code "115") (name "/TCK") (class "Default")
      (node (ref "JTAG") (pin "1") (pinfunction "1_1") (pintype "passive"))
      (node (ref "RP101") (pin "4") (pinfunction "4_4") (pintype "passive"))
      (node (ref "U100") (pin "109") (pinfunction "TCK_109") (pintype "passive"))
    )
    (net (code "116") (name "/TDI") (class "Default")
      (node (ref "JTAG") (pin "9") (pinfunction "9_9") (pintype "passive"))
      (node (ref "RP101") (pin "1") (pinfunction "1_1") (pintype "passive"))
      (node (ref "U100") (pin "110") (pinfunction "TDI_110") (pintype "passive"))
    )
    (net (code "117") (name "/TDO") (class "Default")
      (node (ref "JTAG") (pin "3") (pinfunction "3_3") (pintype "passive"))
      (node (ref "RP101") (pin "3") (pinfunction "3_3") (pintype "passive"))
      (node (ref "U100") (pin "106") (pinfunction "TDO_106") (pintype "passive"))
    )
    (net (code "118") (name "/TMS") (class "Default")
      (node (ref "JTAG") (pin "5") (pinfunction "5_5") (pintype "passive"))
      (node (ref "RP101") (pin "2") (pinfunction "2_2") (pintype "passive"))
      (node (ref "U100") (pin "107") (pinfunction "TMS_107") (pintype "passive"))
    )
    (net (code "119") (name "1V2") (class "Default")
      (node (ref "C112") (pin "2") (pinfunction "2_2") (pintype "passive"))
      (node (ref "C113") (pin "2") (pinfunction "2_2") (pintype "passive"))
      (node (ref "C114") (pin "2") (pinfunction "2_2") (pintype "passive"))
      (node (ref "C115") (pin "2") (pinfunction "2_2") (pintype "passive"))
      (node (ref "C116") (pin "2") (pinfunction "2_2") (pintype "passive"))
      (node (ref "C117") (pin "2") (pinfunction "2_2") (pintype "passive"))
      (node (ref "U100") (pin "128") (pinfunction "VCCINT_128") (pintype "passive"))
      (node (ref "U100") (pin "19") (pinfunction "VCCINT_19") (pintype "passive"))
      (node (ref "U100") (pin "28") (pinfunction "VCCINT_28") (pintype "passive"))
      (node (ref "U100") (pin "52") (pinfunction "VCCINT_52") (pintype "passive"))
      (node (ref "U100") (pin "89") (pinfunction "VCCINT_89") (pintype "passive"))
    )
    (net (code "120") (name "2V5") (class "Default")
      (node (ref "C118") (pin "2") (pinfunction "2_2") (pintype "passive"))
      (node (ref "C119") (pin "2") (pinfunction "2_2") (pintype "passive"))
      (node (ref "C120") (pin "2") (pinfunction "2_2") (pintype "passive"))
      (node (ref "C121") (pin "2") (pinfunction "2_2") (pintype "passive"))
      (node (ref "C122") (pin "2") (pinfunction "2_2") (pintype "passive"))
      (node (ref "C123") (pin "2") (pinfunction "2_2") (pintype "passive"))
      (node (ref "U100") (pin "129") (pinfunction "VCCAUX_129") (pintype "passive"))
      (node (ref "U100") (pin "20") (pinfunction "VCCAUX_20") (pintype "passive"))
      (node (ref "U100") (pin "36") (pinfunction "VCCAUX_36") (pintype "passive"))
      (node (ref "U100") (pin "53") (pinfunction "VCCAUX_53") (pintype "passive"))
      (node (ref "U100") (pin "90") (pinfunction "VCCAUX_90") (pintype "passive"))
    )
    (net (code "121") (name "3V3") (class "Default")
      (node (ref "C100") (pin "2") (pinfunction "2_2") (pintype "passive"))
      (node (ref "C101") (pin "2") (pinfunction "2_2") (pintype "passive"))
      (node (ref "C102") (pin "2") (pinfunction "2_2") (pintype "passive"))
      (node (ref "C103") (pin "2") (pinfunction "2_2") (pintype "passive"))
      (node (ref "C104") (pin "2") (pinfunction "2_2") (pintype "passive"))
      (node (ref "C105") (pin "2") (pinfunction "2_2") (pintype "passive"))
      (node (ref "C106") (pin "2") (pinfunction "2_2") (pintype "passive"))
      (node (ref "C107") (pin "2") (pinfunction "2_2") (pintype "passive"))
      (node (ref "C108") (pin "2") (pinfunction "2_2") (pintype "passive"))
      (node (ref "C109") (pin "2") (pinfunction "2_2") (pintype "passive"))
      (node (ref "C110") (pin "2") (pinfunction "2_2") (pintype "passive"))
      (node (ref "C111") (pin "2") (pinfunction "2_2") (pintype "passive"))
      (node (ref "JTAG") (pin "4") (pinfunction "4_4") (pintype "passive"))
      (node (ref "R101") (pin "2") (pinfunction "2_2") (pintype "passive"))
      (node (ref "R103") (pin "2") (pinfunction "2_2") (pintype "passive"))
      (node (ref "R105") (pin "1") (pinfunction "1_1") (pintype "passive"))
      (node (ref "R110") (pin "1") (pinfunction "1_1") (pintype "passive"))
      (node (ref "R111") (pin "1") (pinfunction "1_1") (pintype "passive"))
      (node (ref "R114") (pin "2") (pinfunction "2_2") (pintype "passive"))
      (node (ref "R115") (pin "2") (pinfunction "2_2") (pintype "passive"))
      (node (ref "R116") (pin "2") (pinfunction "2_2") (pintype "passive"))
      (node (ref "R117") (pin "2") (pinfunction "2_2") (pintype "passive"))
      (node (ref "R118") (pin "2") (pinfunction "2_2") (pintype "passive"))
      (node (ref "RP101") (pin "5") (pinfunction "5_5") (pintype "passive"))
      (node (ref "RP101") (pin "6") (pinfunction "6_6") (pintype "passive"))
      (node (ref "RP101") (pin "7") (pinfunction "7_7") (pintype "passive"))
      (node (ref "RP101") (pin "8") (pinfunction "8_8") (pintype "passive"))
      (node (ref "RP102") (pin "5") (pinfunction "5_5") (pintype "passive"))
      (node (ref "RP102") (pin "6") (pinfunction "6_6") (pintype "passive"))
      (node (ref "RP102") (pin "7") (pinfunction "7_7") (pintype "passive"))
      (node (ref "U100") (pin "103") (pinfunction "VCC_IO_1_103") (pintype "passive"))
      (node (ref "U100") (pin "122") (pinfunction "VCC_IO_0_122") (pintype "passive"))
      (node (ref "U100") (pin "125") (pinfunction "VCC_IO_0_125") (pintype "passive"))
      (node (ref "U100") (pin "135") (pinfunction "VCC_IO_0_135") (pintype "passive"))
      (node (ref "U100") (pin "18") (pinfunction "VCC_IO_3_18") (pintype "passive"))
      (node (ref "U100") (pin "31") (pinfunction "VCC_IO_3_31") (pintype "passive"))
      (node (ref "U100") (pin "4") (pinfunction "VCC_IO_3_4") (pintype "passive"))
      (node (ref "U100") (pin "42") (pinfunction "VCC_IO_2_42") (pintype "passive"))
      (node (ref "U100") (pin "63") (pinfunction "VCC_IO_2_63") (pintype "passive"))
      (node (ref "U100") (pin "76") (pinfunction "VCC_IO_1_76") (pintype "passive"))
      (node (ref "U100") (pin "86") (pinfunction "VCC_IO_1_86") (pintype "passive"))
      (node (ref "U101") (pin "8") (pinfunction "VCC_8") (pintype "passive"))
    )
    (net (code "122") (name "GND") (class "Default")
      (node (ref "C100") (pin "1") (pinfunction "1_1") (pintype "passive"))
      (node (ref "C101") (pin "1") (pinfunction "1_1") (pintype "passive"))
      (node (ref "C102") (pin "1") (pinfunction "1_1") (pintype "passive"))
      (node (ref "C103") (pin "1") (pinfunction "1_1") (pintype "passive"))
      (node (ref "C104") (pin "1") (pinfunction "1_1") (pintype "passive"))
      (node (ref "C105") (pin "1") (pinfunction "1_1") (pintype "passive"))
      (node (ref "C106") (pin "1") (pinfunction "1_1") (pintype "passive"))
      (node (ref "C107") (pin "1") (pinfunction "1_1") (pintype "passive"))
      (node (ref "C108") (pin "1") (pinfunction "1_1") (pintype "passive"))
      (node (ref "C109") (pin "1") (pinfunction "1_1") (pintype "passive"))
      (node (ref "C110") (pin "1") (pinfunction "1_1") (pintype "passive"))
      (node (ref "C111") (pin "1") (pinfunction "1_1") (pintype "passive"))
      (node (ref "C112") (pin "1") (pinfunction "1_1") (pintype "passive"))
      (node (ref "C113") (pin "1") (pinfunction "1_1") (pintype "passive"))
      (node (ref "C114") (pin "1") (pinfunction "1_1") (pintype "passive"))
      (node (ref "C115") (pin "1") (pinfunction "1_1") (pintype "passive"))
      (node (ref "C116") (pin "1") (pinfunction "1_1") (pintype "passive"))
      (node (ref "C117") (pin "1") (pinfunction "1_1") (pintype "passive"))
      (node (ref "C118") (pin "1") (pinfunction "1_1") (pintype "passive"))
      (node (ref "C119") (pin "1") (pinfunction "1_1") (pintype "passive"))
      (node (ref "C120") (pin "1") (pinfunction "1_1") (pintype "passive"))
      (node (ref "C121") (pin "1") (pinfunction "1_1") (pintype "passive"))
      (node (ref "C122") (pin "1") (pinfunction "1_1") (pintype "passive"))
      (node (ref "C123") (pin "1") (pinfunction "1_1") (pintype "passive"))
      (node (ref "JTAG") (pin "10") (pinfunction "10_10") (pintype "passive"))
      (node (ref "JTAG") (pin "2") (pinfunction "2_2") (pintype "passive"))
      (node (ref "R109") (pin "1") (pinfunction "1_1") (pintype "passive"))
      (node (ref "R112") (pin "1") (pinfunction "1_1") (pintype "passive"))
      (node (ref "U100") (pin "108") (pinfunction "GND_108") (pintype "passive"))
      (node (ref "U100") (pin "113") (pinfunction "GND_113") (pintype "passive"))
      (node (ref "U100") (pin "13") (pinfunction "GND_13") (pintype "passive"))
      (node (ref "U100") (pin "130") (pinfunction "GND_130") (pintype "passive"))
      (node (ref "U100") (pin "136") (pinfunction "GND_136") (pintype "passive"))
      (node (ref "U100") (pin "25") (pinfunction "GND_25") (pintype "passive"))
      (node (ref "U100") (pin "3") (pinfunction "GND_3") (pintype "passive"))
      (node (ref "U100") (pin "49") (pinfunction "GND_49") (pintype "passive"))
      (node (ref "U100") (pin "54") (pinfunction "GND_54") (pintype "passive"))
      (node (ref "U100") (pin "68") (pinfunction "GND_68") (pintype "passive"))
      (node (ref "U100") (pin "72") (pinfunction "CMPCS_B_72") (pintype "passive"))
      (node (ref "U100") (pin "73") (pinfunction "SUSPEND_73") (pintype "passive"))
      (node (ref "U100") (pin "77") (pinfunction "GND_77") (pintype "passive"))
      (node (ref "U100") (pin "91") (pinfunction "GND_91") (pintype "passive"))
      (node (ref "U100") (pin "96") (pinfunction "GND_96") (pintype "passive"))
      (node (ref "U101") (pin "4") (pinfunction "GND_4") (pintype "passive"))
      (node (ref "X100") (pin "2") (pinfunction "GND_2") (pintype "passive"))
    )
    (net (code "123") (name "Net-(D101-A)") (class "Default")
      (node (ref "D101") (pin "1") (pinfunction "A_1") (pintype "passive"))
      (node (ref "R103") (pin "1") (pinfunction "1_1") (pintype "passive"))
    )
    (net (code "124") (name "Net-(D102-A)") (class "Default")
      (node (ref "D102") (pin "1") (pinfunction "A_1") (pintype "passive"))
      (node (ref "R114") (pin "1") (pinfunction "1_1") (pintype "passive"))
    )
    (net (code "125") (name "Net-(D103-A)") (class "Default")
      (node (ref "D103") (pin "1") (pinfunction "A_1") (pintype "passive"))
      (node (ref "R115") (pin "1") (pinfunction "1_1") (pintype "passive"))
    )
    (net (code "126") (name "Net-(D104-A)") (class "Default")
      (node (ref "D104") (pin "1") (pinfunction "A_1") (pintype "passive"))
      (node (ref "R116") (pin "1") (pinfunction "1_1") (pintype "passive"))
    )
    (net (code "127") (name "Net-(D105-A)") (class "Default")
      (node (ref "D105") (pin "1") (pinfunction "A_1") (pintype "passive"))
      (node (ref "R117") (pin "1") (pinfunction "1_1") (pintype "passive"))
    )
    (net (code "128") (name "Net-(U101-CLK)") (class "Default")
      (node (ref "R108") (pin "2") (pinfunction "2_2") (pintype "passive"))
      (node (ref "U101") (pin "6") (pinfunction "CLK_6") (pintype "passive"))
    )
    (net (code "129") (name "Net-(U101-DIO)") (class "Default")
      (node (ref "R107") (pin "2") (pinfunction "2_2") (pintype "passive"))
      (node (ref "U101") (pin "5") (pinfunction "DIO_5") (pintype "passive"))
    )
    (net (code "130") (name "Net-(U101-DO)") (class "Default")
      (node (ref "R106") (pin "2") (pinfunction "2_2") (pintype "passive"))
      (node (ref "U101") (pin "2") (pinfunction "DO_2") (pintype "passive"))
    )
    (net (code "131") (name "Net-(U101-~{HOLD})") (class "Default")
      (node (ref "RP102") (pin "4") (pinfunction "4_4") (pintype "passive"))
      (node (ref "U101") (pin "7") (pinfunction "~{HOLD}_7") (pintype "passive"))
    )
    (net (code "132") (name "Net-(U101-~{WP})") (class "Default")
      (node (ref "RP102") (pin "2") (pinfunction "2_2") (pintype "passive"))
      (node (ref "U101") (pin "3") (pinfunction "~{WP}_3") (pintype "passive"))
    )
    (net (code "133") (name "Net-(X100-CLK)") (class "Default")
      (node (ref "R104") (pin "1") (pinfunction "1_1") (pintype "passive"))
      (node (ref "X100") (pin "3") (pinfunction "CLK_3") (pintype "passive"))
    )
    (net (code "134") (name "Net-(X100-VDD)") (class "Default")
      (node (ref "R105") (pin "2") (pinfunction "2_2") (pintype "passive"))
      (node (ref "X100") (pin "4") (pinfunction "VDD_4") (pintype "passive"))
    )
    (net (code "135") (name "unconnected-(JTAG-Pad6)") (class "Default")
      (node (ref "JTAG") (pin "6") (pinfunction "6_6") (pintype "passive+no_connect"))
    )
    (net (code "136") (name "unconnected-(JTAG-Pad7)") (class "Default")
      (node (ref "JTAG") (pin "7") (pinfunction "7_7") (pintype "passive+no_connect"))
    )
    (net (code "137") (name "unconnected-(JTAG-Pad8)") (class "Default")
      (node (ref "JTAG") (pin "8") (pinfunction "8_8") (pintype "passive+no_connect"))
    )
    (net (code "138") (name "unconnected-(RP102-Pad1)") (class "Default")
      (node (ref "RP102") (pin "1") (pinfunction "1_1") (pintype "passive+no_connect"))
    )
    (net (code "139") (name "unconnected-(RP102-Pad8)") (class "Default")
      (node (ref "RP102") (pin "8") (pinfunction "8_8") (pintype "passive+no_connect"))
    )
    (net (code "140") (name "unconnected-(RP104-Pad4)") (class "Default")
      (node (ref "RP104") (pin "4") (pinfunction "4_4") (pintype "passive+no_connect"))
    )
    (net (code "141") (name "unconnected-(RP104-Pad5)") (class "Default")
      (node (ref "RP104") (pin "5") (pinfunction "5_5") (pintype "passive+no_connect"))
    )
    (net (code "142") (name "unconnected-(RP107-Pad2)") (class "Default")
      (node (ref "RP107") (pin "2") (pinfunction "2_2") (pintype "passive+no_connect"))
    )
    (net (code "143") (name "unconnected-(RP107-Pad3)") (class "Default")
      (node (ref "RP107") (pin "3") (pinfunction "3_3") (pintype "passive+no_connect"))
    )
    (net (code "144") (name "unconnected-(RP107-Pad6)") (class "Default")
      (node (ref "RP107") (pin "6") (pinfunction "6_6") (pintype "passive+no_connect"))
    )
    (net (code "145") (name "unconnected-(RP107-Pad7)") (class "Default")
      (node (ref "RP107") (pin "7") (pinfunction "7_7") (pintype "passive+no_connect"))
    )
    (net (code "146") (name "unconnected-(U100A-IO_L1N+VREF-Pad143)") (class "Default")
      (node (ref "U100") (pin "143") (pinfunction "IO_L1N+VREF_143") (pintype "passive"))
    )
    (net (code "147") (name "unconnected-(U100A-IO_L2N-Pad141)") (class "Default")
      (node (ref "U100") (pin "141") (pinfunction "IO_L2N_141") (pintype "passive"))
    )
    (net (code "148") (name "unconnected-(U100A-IO_L2P-Pad142)") (class "Default")
      (node (ref "U100") (pin "142") (pinfunction "IO_L2P_142") (pintype "passive"))
    )
    (net (code "149") (name "unconnected-(U100A-IO_L34N_GCLK18-Pad133)") (class "Default")
      (node (ref "U100") (pin "133") (pinfunction "IO_L34N_GCLK18_133") (pintype "passive"))
    )
    (net (code "150") (name "unconnected-(U100A-IO_L34P_GCLK19-Pad134)") (class "Default")
      (node (ref "U100") (pin "134") (pinfunction "IO_L34P_GCLK19_134") (pintype "passive"))
    )
    (net (code "151") (name "unconnected-(U100A-IO_L35N_GCLK16-Pad131)") (class "Default")
      (node (ref "U100") (pin "131") (pinfunction "IO_L35N_GCLK16_131") (pintype "passive"))
    )
    (net (code "152") (name "unconnected-(U100A-IO_L35P_GCLK17-Pad132)") (class "Default")
      (node (ref "U100") (pin "132") (pinfunction "IO_L35P_GCLK17_132") (pintype "passive"))
    )
    (net (code "153") (name "unconnected-(U100A-IO_L36P_GCLK15-Pad127)") (class "Default")
      (node (ref "U100") (pin "127") (pinfunction "IO_L36P_GCLK15_127") (pintype "passive"))
    )
    (net (code "154") (name "unconnected-(U100A-IO_L37P_GCLK13-Pad124)") (class "Default")
      (node (ref "U100") (pin "124") (pinfunction "IO_L37P_GCLK13_124") (pintype "passive"))
    )
    (net (code "155") (name "unconnected-(U100A-IO_L64N-Pad116)") (class "Default")
      (node (ref "U100") (pin "116") (pinfunction "IO_L64N_116") (pintype "passive"))
    )
    (net (code "156") (name "unconnected-(U100C-IO_L2N_CMPMOSI-Pad66)") (class "Default")
      (node (ref "U100") (pin "66") (pinfunction "IO_L2N_CMPMOSI_66") (pintype "passive"))
    )
    (net (code "157") (name "unconnected-(U100C-IO_L2P_CMPCLK-Pad67)") (class "Default")
      (node (ref "U100") (pin "67") (pinfunction "IO_L2P_CMPCLK_67") (pintype "passive"))
    )
    (net (code "158") (name "unconnected-(U100C-IO_L12N_MISO3-Pad61)") (class "Default")
      (node (ref "U100") (pin "61") (pinfunction "IO_L12N_MISO3_61") (pintype "passive"))
    )
    (net (code "159") (name "unconnected-(U100C-IO_L12P_MISO2-Pad62)") (class "Default")
      (node (ref "U100") (pin "62") (pinfunction "IO_L12P_MISO2_62") (pintype "passive"))
    )
    (net (code "160") (name "unconnected-(U100C-IO_L13N-Pad59)") (class "Default")
      (node (ref "U100") (pin "59") (pinfunction "IO_L13N_59") (pintype "passive"))
    )
    (net (code "161") (name "unconnected-(U100C-IO_L14P-Pad58)") (class "Default")
      (node (ref "U100") (pin "58") (pinfunction "IO_L14P_58") (pintype "passive"))
    )
    (net (code "162") (name "unconnected-(U100C-IO_L64N-Pad40)") (class "Default")
      (node (ref "U100") (pin "40") (pinfunction "IO_L64N_40") (pintype "passive"))
    )
    (net (code "163") (name "unconnected-(U100C-IO_L64P-Pad41)") (class "Default")
      (node (ref "U100") (pin "41") (pinfunction "IO_L64P_41") (pintype "passive"))
    )
    (net (code "164") (name "unconnected-(U100D-IO_L1N_VREF-Pad34)") (class "Default")
      (node (ref "U100") (pin "34") (pinfunction "IO_L1N_VREF_34") (pintype "passive"))
    )
    (net (code "165") (name "unconnected-(U100D-IO_L1P-Pad35)") (class "Default")
      (node (ref "U100") (pin "35") (pinfunction "IO_L1P_35") (pintype "passive"))
    )
    (net (code "166") (name "unconnected-(U100D-IO_L2N-Pad32)") (class "Default")
      (node (ref "U100") (pin "32") (pinfunction "IO_L2N_32") (pintype "passive"))
    )
    (net (code "167") (name "unconnected-(U100D-IO_L2P-Pad33)") (class "Default")
      (node (ref "U100") (pin "33") (pinfunction "IO_L2P_33") (pintype "passive"))
    )
    (net (code "168") (name "unconnected-(U100D-IO_L83N_VREF-Pad1)") (class "Default")
      (node (ref "U100") (pin "1") (pinfunction "IO_L83N_VREF_1") (pintype "passive"))
    )
    (net (code "169") (name "unconnected-(U100D-IO_L83P-Pad2)") (class "Default")
      (node (ref "U100") (pin "2") (pinfunction "IO_L83P_2") (pintype "passive"))
    )
    (net (code "170") (name "unconnected-(X100-E{slash}D-Pad1)") (class "Default")
      (node (ref "X100") (pin "1") (pinfunction "E/D_1") (pintype "passive"))
    )
  )
)
